# interface.net
KiCad netlist of a schematic drawn in Altium Designer
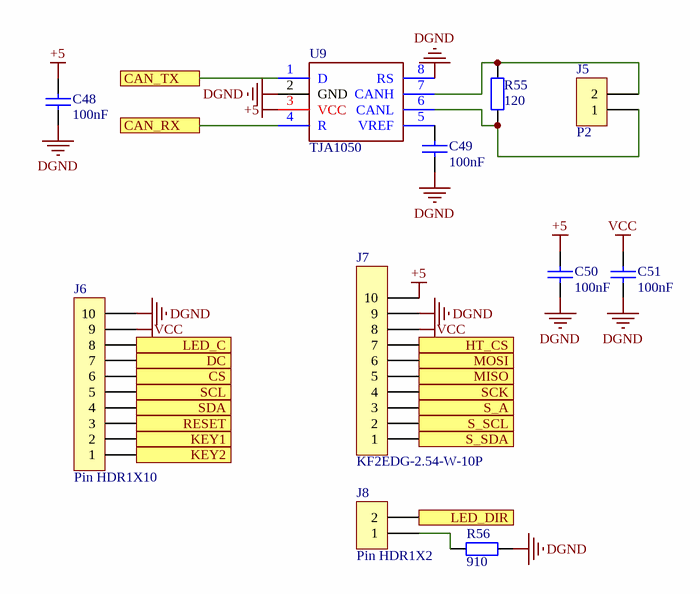
[diagram p0: interface.SchDoc]

(export (version "E")
  (design (tool "Eeschema 10.0.6"))
  (components
    (comp (ref "C48")
      (value "100nF")
      (footprint "C 0402_L")
      (description "无极性电容")
      (fields (field (name "Comment") "Cap") (field (name "PUBLISHER") "Altium Limited"))
      (libsource (lib "CAP") (part "C0402"))
    )
    (comp (ref "C49")
      (value "100nF")
      (footprint "C 0402_L")
      (description "无极性电容")
      (fields (field (name "Comment") "Cap") (field (name "PUBLISHER") "Altium Limited"))
      (libsource (lib "CAP") (part "C0402"))
    )
    (comp (ref "C50")
      (value "100nF")
      (footprint "C 0402_L")
      (description "无极性电容")
      (fields (field (name "Comment") "Cap") (field (name "PUBLISHER") "Altium Limited"))
      (libsource (lib "CAP") (part "C0402"))
    )
    (comp (ref "C51")
      (value "100nF")
      (footprint "C 0402_L")
      (description "无极性电容")
      (fields (field (name "Comment") "Cap") (field (name "PUBLISHER") "Altium Limited"))
      (libsource (lib "CAP") (part "C0402"))
    )
    (comp (ref "J5")
      (value "P2")
      (footprint "KF2EDGK-2.54W-2P")
      (description "弯针")
      (libsource (lib "接插件") (part "KF2EDG-2.54-W-2P"))
    )
    (comp (ref "J6")
      (value "Pin HDR1X10")
      (footprint "FPC0.5 2H-WS-10P")
      (libsource (lib "排针") (part "Pin HDR1X10"))
    )
    (comp (ref "J7")
      (value "KF2EDG-2.54-W-10P")
      (footprint "KF2EDGK-2.54W-10P")
      (libsource (lib "接插件") (part "KF2EDG-2.54-W-10P"))
    )
    (comp (ref "J8")
      (value "Pin HDR1X2")
      (footprint "Pin HDR1X2/2.54mm-S")
      (libsource (lib "排针") (part "Pin HDR1X2"))
    )
    (comp (ref "R55")
      (value "120")
      (footprint "0402R")
      (description "贴片电阻")
      (fields (field (name "Comment") "Res1") (field (name "PUBLISHER") "Altium Limited"))
      (libsource (lib "") (part "R0402_1"))
    )
    (comp (ref "R56")
      (value "910")
      (footprint "0402R")
      (description "贴片电阻")
      (fields (field (name "Comment") "Res1") (field (name "PUBLISHER") "Altium Limited"))
      (libsource (lib "RES") (part "R0402"))
    )
    (comp (ref "U9") (value "TJA1050") (footprint "SOP8_M") (libsource (lib "MCU") (part "SN65HVD230DR")))
  )
  (nets
    (net (code "1") (name "+5") (class "Default")
      (node (ref "C48") (pin "2") (pinfunction "2_2") (pintype "passive"))
      (node (ref "C50") (pin "2") (pinfunction "2_2") (pintype "passive"))
      (node (ref "J7") (pin "10") (pinfunction "10_10") (pintype "passive"))
      (node (ref "U9") (pin "3") (pinfunction "VCC_3") (pintype "passive"))
    )
    (net (code "2") (name "/CAN_RX") (class "Default")
      (node (ref "U9") (pin "4") (pinfunction "R_4") (pintype "passive"))
    )
    (net (code "3") (name "/CAN_TX") (class "Default")
      (node (ref "U9") (pin "1") (pinfunction "D_1") (pintype "passive"))
    )
    (net (code "4") (name "/CS") (class "Default")
      (node (ref "J6") (pin "6") (pinfunction "6_6") (pintype "passive"))
    )
    (net (code "5") (name "/DC") (class "Default")
      (node (ref "J6") (pin "7") (pinfunction "7_7") (pintype "passive"))
    )
    (net (code "6") (name "/HT_CS") (class "Default")
      (node (ref "J7") (pin "7") (pinfunction "7_7") (pintype "passive"))
    )
    (net (code "7") (name "/KEY1") (class "Default")
      (node (ref "J6") (pin "2") (pinfunction "2_2") (pintype "passive"))
    )
    (net (code "8") (name "/KEY2") (class "Default")
      (node (ref "J6") (pin "1") (pinfunction "1_1") (pintype "passive"))
    )
    (net (code "9") (name "/LED_C") (class "Default")
      (node (ref "J6") (pin "8") (pinfunction "8_8") (pintype "passive"))
    )
    (net (code "10") (name "/LED_DIR") (class "Default")
      (node (ref "J8") (pin "2") (pinfunction "2_2") (pintype "passive"))
    )
    (net (code "11") (name "/MISO") (class "Default")
      (node (ref "J7") (pin "5") (pinfunction "5_5") (pintype "passive"))
    )
    (net (code "12") (name "/MOSI") (class "Default")
      (node (ref "J7") (pin "6") (pinfunction "6_6") (pintype "passive"))
    )
    (net (code "13") (name "/RESET") (class "Default")
      (node (ref "J6") (pin "3") (pinfunction "3_3") (pintype "passive"))
    )
    (net (code "14") (name "/SCK") (class "Default")
      (node (ref "J7") (pin "4") (pinfunction "4_4") (pintype "passive"))
    )
    (net (code "15") (name "/SCL") (class "Default")
      (node (ref "J6") (pin "5") (pinfunction "5_5") (pintype "passive"))
    )
    (net (code "16") (name "/SDA") (class "Default")
      (node (ref "J6") (pin "4") (pinfunction "4_4") (pintype "passive"))
    )
    (net (code "17") (name "/S_A") (class "Default")
      (node (ref "J7") (pin "3") (pinfunction "3_3") (pintype "passive"))
    )
    (net (code "18") (name "/S_SCL") (class "Default")
      (node (ref "J7") (pin "2") (pinfunction "2_2") (pintype "passive"))
    )
    (net (code "19") (name "/S_SDA") (class "Default")
      (node (ref "J7") (pin "1") (pinfunction "1_1") (pintype "passive"))
    )
    (net (code "20") (name "DGND") (class "Default")
      (node (ref "C48") (pin "1") (pinfunction "1_1") (pintype "passive"))
      (node (ref "C49") (pin "1") (pinfunction "1_1") (pintype "passive"))
      (node (ref "C50") (pin "1") (pinfunction "1_1") (pintype "passive"))
      (node (ref "C51") (pin "1") (pinfunction "1_1") (pintype "passive"))
      (node (ref "J6") (pin "10") (pinfunction "10_10") (pintype "passive"))
      (node (ref "J7") (pin "9") (pinfunction "9_9") (pintype "passive"))
      (node (ref "R56") (pin "2") (pinfunction "2_2") (pintype "passive"))
      (node (ref "U9") (pin "2") (pinfunction "GND_2") (pintype "passive"))
      (node (ref "U9") (pin "8") (pinfunction "RS_8") (pintype "passive"))
    )
    (net (code "21") (name "Net-(J8-Pad1)") (class "Default")
      (node (ref "J8") (pin "1") (pinfunction "1_1") (pintype "passive"))
      (node (ref "R56") (pin "1") (pinfunction "1_1") (pintype "passive"))
    )
    (net (code "22") (name "Net-(U9-CANH)") (class "Default")
      (node (ref "J5") (pin "2") (pinfunction "2_2") (pintype "passive"))
      (node (ref "R55") (pin "2") (pinfunction "2_2") (pintype "passive"))
      (node (ref "U9") (pin "7") (pinfunction "CANH_7") (pintype "passive"))
    )
    (net (code "23") (name "Net-(U9-CANL)") (class "Default")
      (node (ref "J5") (pin "1") (pinfunction "1_1") (pintype "passive"))
      (node (ref "R55") (pin "1") (pinfunction "1_1") (pintype "passive"))
      (node (ref "U9") (pin "6") (pinfunction "CANL_6") (pintype "passive"))
    )
    (net (code "24") (name "Net-(U9-VREF)") (class "Default")
      (node (ref "C49") (pin "2") (pinfunction "2_2") (pintype "passive"))
      (node (ref "U9") (pin "5") (pinfunction "VREF_5") (pintype "passive"))
    )
    (net (code "25") (name "VCC") (class "Default")
      (node (ref "C51") (pin "2") (pinfunction "2_2") (pintype "passive"))
      (node (ref "J6") (pin "9") (pinfunction "9_9") (pintype "passive"))
      (node (ref "J7") (pin "8") (pinfunction "8_8") (pintype "passive"))
    )
  )
)
